# lp_numi.net
KiCad netlist of a schematic drawn in EAGLE
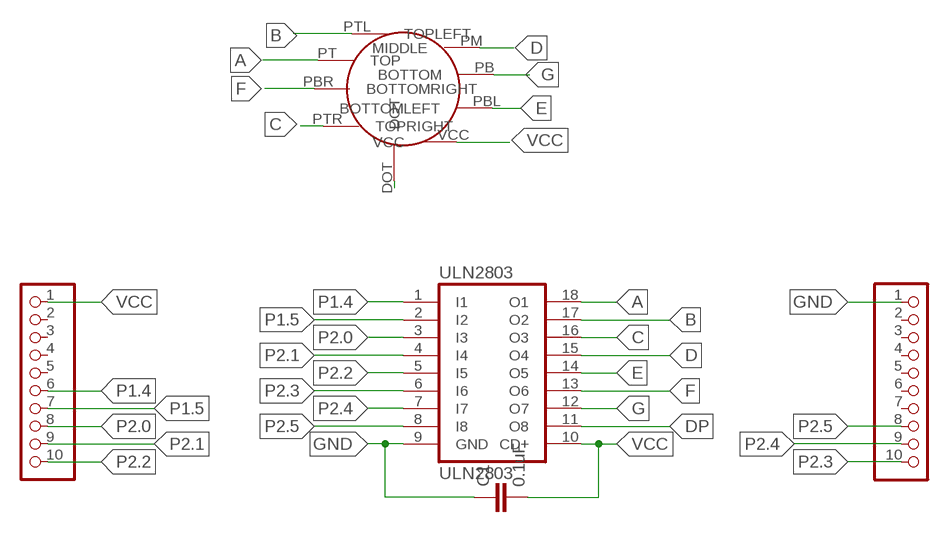
[diagram p0: schematic, sheet 1]

(export (version "E")
  (design (tool "Eeschema 10.0.6"))
  (components
    (comp (ref "C1")
      (value "0.1uF")
      (footprint "eagle-import:C025-025X050")
      (libsource (lib "eagle-import") (part "C-EU025-025X050"))
    )
    (comp (ref "J1")
      (value "J1")
      (footprint "eagle-import:1X10")
      (libsource (lib "eagle-import") (part "PINHD-1X10"))
    )
    (comp (ref "J2")
      (value "J2")
      (footprint "eagle-import:1X10")
      (libsource (lib "eagle-import") (part "PINHD-1X10"))
    )
    (comp (ref "U$2")
      (value "IV16TINY_NUMITRON")
      (footprint "eagle-import:IV16TINY_NUMITRON_PAC")
      (libsource (lib "eagle-import") (part "IV16TINY_NUMITRON"))
    )
    (comp (ref "ULN2803")
      (value "ULN2803")
      (footprint "eagle-import:DIL18")
      (libsource (lib "eagle-import") (part "ULN2803A"))
    )
  )
  (nets
    (net (code "1") (name "A") (class "Default")
      (node (ref "U$2") (pin "PT") (pinfunction "TOP_PT") (pintype "input"))
      (node (ref "ULN2803") (pin "18") (pinfunction "O1_18") (pintype "open_collector"))
    )
    (net (code "2") (name "B") (class "Default")
      (node (ref "U$2") (pin "PTL") (pinfunction "TOPLEFT_PTL") (pintype "input"))
      (node (ref "ULN2803") (pin "17") (pinfunction "O2_17") (pintype "open_collector"))
    )
    (net (code "3") (name "C") (class "Default")
      (node (ref "U$2") (pin "PTR") (pinfunction "TOPRIGHT_PTR") (pintype "input"))
      (node (ref "ULN2803") (pin "16") (pinfunction "O3_16") (pintype "open_collector"))
    )
    (net (code "4") (name "D") (class "Default")
      (node (ref "U$2") (pin "PM") (pinfunction "MIDDLE_PM") (pintype "input"))
      (node (ref "ULN2803") (pin "15") (pinfunction "O4_15") (pintype "open_collector"))
    )
    (net (code "5") (name "DP") (class "Default")
      (node (ref "U$2") (pin "DOT") (pinfunction "DOT_DOT") (pintype "bidirectional"))
      (node (ref "ULN2803") (pin "11") (pinfunction "O8_11") (pintype "open_collector"))
    )
    (net (code "6") (name "E") (class "Default")
      (node (ref "U$2") (pin "PBL") (pinfunction "BOTTOMLEFT_PBL") (pintype "input"))
      (node (ref "ULN2803") (pin "14") (pinfunction "O5_14") (pintype "open_collector"))
    )
    (net (code "7") (name "F") (class "Default")
      (node (ref "U$2") (pin "PBR") (pinfunction "BOTTOMRIGHT_PBR") (pintype "input"))
      (node (ref "ULN2803") (pin "13") (pinfunction "O6_13") (pintype "open_collector"))
    )
    (net (code "8") (name "G") (class "Default")
      (node (ref "U$2") (pin "PB") (pinfunction "BOTTOM_PB") (pintype "input"))
      (node (ref "ULN2803") (pin "12") (pinfunction "O7_12") (pintype "open_collector"))
    )
    (net (code "9") (name "GND") (class "Default")
      (node (ref "C1") (pin "1") (pinfunction "1_1") (pintype "passive"))
      (node (ref "J2") (pin "1") (pinfunction "1_1") (pintype "passive"))
      (node (ref "ULN2803") (pin "9") (pinfunction "GND_9") (pintype "power_in"))
    )
    (net (code "10") (name "P1.4") (class "Default")
      (node (ref "J1") (pin "6") (pinfunction "6_6") (pintype "passive"))
      (node (ref "ULN2803") (pin "1") (pinfunction "I1_1") (pintype "input"))
    )
    (net (code "11") (name "P1.5") (class "Default")
      (node (ref "J1") (pin "7") (pinfunction "7_7") (pintype "passive"))
      (node (ref "ULN2803") (pin "2") (pinfunction "I2_2") (pintype "input"))
    )
    (net (code "12") (name "P2.0") (class "Default")
      (node (ref "J1") (pin "8") (pinfunction "8_8") (pintype "passive"))
      (node (ref "ULN2803") (pin "3") (pinfunction "I3_3") (pintype "input"))
    )
    (net (code "13") (name "P2.1") (class "Default")
      (node (ref "J1") (pin "9") (pinfunction "9_9") (pintype "passive"))
      (node (ref "ULN2803") (pin "4") (pinfunction "I4_4") (pintype "input"))
    )
    (net (code "14") (name "P2.2") (class "Default")
      (node (ref "J1") (pin "10") (pinfunction "10_10") (pintype "passive"))
      (node (ref "ULN2803") (pin "5") (pinfunction "I5_5") (pintype "input"))
    )
    (net (code "15") (name "P2.3") (class "Default")
      (node (ref "J2") (pin "10") (pinfunction "10_10") (pintype "passive"))
      (node (ref "ULN2803") (pin "6") (pinfunction "I6_6") (pintype "input"))
    )
    (net (code "16") (name "P2.4") (class "Default")
      (node (ref "J2") (pin "9") (pinfunction "9_9") (pintype "passive"))
      (node (ref "ULN2803") (pin "7") (pinfunction "I7_7") (pintype "input"))
    )
    (net (code "17") (name "P2.5") (class "Default")
      (node (ref "J2") (pin "8") (pinfunction "8_8") (pintype "passive"))
      (node (ref "ULN2803") (pin "8") (pinfunction "I8_8") (pintype "input"))
    )
    (net (code "18") (name "VCC") (class "Default")
      (node (ref "C1") (pin "2") (pinfunction "2_2") (pintype "passive"))
      (node (ref "J1") (pin "1") (pinfunction "1_1") (pintype "passive"))
      (node (ref "U$2") (pin "VCC") (pinfunction "VCC_VCC") (pintype "input"))
      (node (ref "ULN2803") (pin "10") (pinfunction "CD+_10") (pintype "passive"))
    )
    (net (code "19") (name "unconnected-(J1-Pad2)") (class "Default")
      (node (ref "J1") (pin "2") (pinfunction "2_2") (pintype "passive"))
    )
    (net (code "20") (name "unconnected-(J1-Pad3)") (class "Default")
      (node (ref "J1") (pin "3") (pinfunction "3_3") (pintype "passive"))
    )
    (net (code "21") (name "unconnected-(J1-Pad4)") (class "Default")
      (node (ref "J1") (pin "4") (pinfunction "4_4") (pintype "passive"))
    )
    (net (code "22") (name "unconnected-(J1-Pad5)") (class "Default")
      (node (ref "J1") (pin "5") (pinfunction "5_5") (pintype "passive"))
    )
    (net (code "23") (name "unconnected-(J2-Pad2)") (class "Default")
      (node (ref "J2") (pin "2") (pinfunction "2_2") (pintype "passive"))
    )
    (net (code "24") (name "unconnected-(J2-Pad3)") (class "Default")
      (node (ref "J2") (pin "3") (pinfunction "3_3") (pintype "passive"))
    )
    (net (code "25") (name "unconnected-(J2-Pad4)") (class "Default")
      (node (ref "J2") (pin "4") (pinfunction "4_4") (pintype "passive"))
    )
    (net (code "26") (name "unconnected-(J2-Pad5)") (class "Default")
      (node (ref "J2") (pin "5") (pinfunction "5_5") (pintype "passive"))
    )
    (net (code "27") (name "unconnected-(J2-Pad6)") (class "Default")
      (node (ref "J2") (pin "6") (pinfunction "6_6") (pintype "passive"))
    )
    (net (code "28") (name "unconnected-(J2-Pad7)") (class "Default")
      (node (ref "J2") (pin "7") (pinfunction "7_7") (pintype "passive"))
    )
  )
)
